# Sheet1.net
KiCad netlist of a schematic drawn in Altium Designer
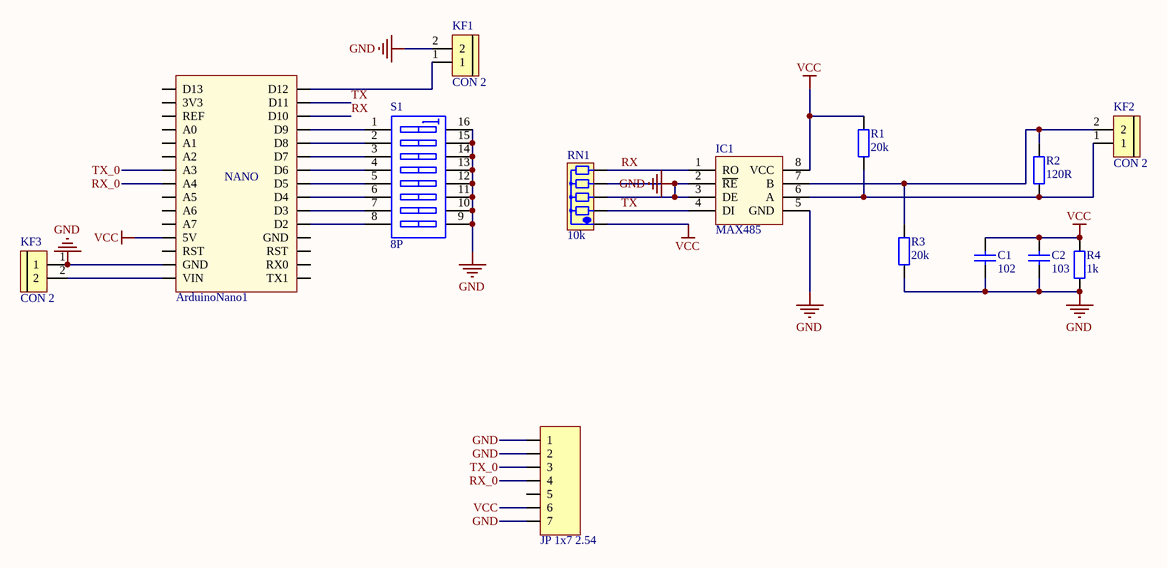
[diagram p0: Sheet1.SchDoc]

(export (version "E")
  (design (tool "Eeschema 10.0.6"))
  (components
    (comp (ref "ArduinoNano1")
      (value "Arduino Nano")
      (footprint "Arduino Nano")
      (description "Arduino NANO")
      (libsource (lib "LIBRARY") (part "Arduino Nano"))
    )
    (comp (ref "C1")
      (value "102")
      (footprint "tu gom")
      (description "Cắm")
      (libsource (lib "Altium_Lib_by_KhueNguyenCreator") (part "Tu gom 102 50V"))
    )
    (comp (ref "C2")
      (value "103")
      (footprint "tu gom")
      (description "Cắm")
      (libsource (lib "Altium_Lib_by_KhueNguyenCreator") (part "Tu gom 103 50V"))
    )
    (comp (ref "IC1")
      (value "MAX485")
      (footprint "DIP8/W0.3")
      (description "RS232 - RS485 (Same sn75176)")
      (libsource (lib "My Library") (part "MAX485"))
    )
    (comp (ref "JP1")
      (value "JP 1x7 2.54")
      (footprint "JP 1x7 CT")
      (description "Cắm")
      (libsource (lib "Altium_Lib_by_KhueNguyenCreator") (part "JP 1x7 2.54 Cai Thang"))
    )
    (comp (ref "KF1")
      (value "CON 2")
      (footprint "Con 2 KF301 5.08")
      (description "Cắm")
      (libsource (lib "Altium_Lib_by_KhueNguyenCreator") (part "CON 2 KF301"))
    )
    (comp (ref "KF2")
      (value "CON 2")
      (footprint "Con 2 KF301 5.08")
      (description "Cắm")
      (libsource (lib "Altium_Lib_by_KhueNguyenCreator") (part "CON 2 KF301"))
    )
    (comp (ref "KF3")
      (value "CON 2")
      (footprint "Con 2 KF301 5.08")
      (description "Cắm")
      (libsource (lib "") (part "CON 2 KF301_1"))
    )
    (comp (ref "R1")
      (value "20k")
      (footprint "tro vach 1/4w")
      (description "Cắm")
      (libsource (lib "Altium_Lib_by_KhueNguyenCreator") (part "Tro Vach 1/4W 5% 20k"))
    )
    (comp (ref "R2")
      (value "120R")
      (footprint "tro vach 1/4w")
      (description "Cắm")
      (libsource (lib "Altium_Lib_by_KhueNguyenCreator") (part "Tro Vach 1/4W 5% 120R"))
    )
    (comp (ref "R3")
      (value "20k")
      (footprint "tro vach 1/4w")
      (description "Cắm")
      (libsource (lib "Altium_Lib_by_KhueNguyenCreator") (part "Tro Vach 1/4W 5% 20k"))
    )
    (comp (ref "R4")
      (value "1k")
      (footprint "tro vach 1/4w")
      (description "Cắm")
      (libsource (lib "Altium_Lib_by_KhueNguyenCreator") (part "Tro Vach 1/4W 5% 1k"))
    )
    (comp (ref "RN1")
      (value "10k")
      (footprint "RN4")
      (description "Resistor 4 (thanh)")
      (libsource (lib "Cty1") (part "RN4"))
    )
    (comp (ref "S1")
      (value "8P")
      (footprint "SW-DIP8")
      (description "Cắm")
      (libsource (lib "THU VIEN SCH") (part "Cong Tac Bits 8P"))
    )
  )
  (nets
    (net (code "1") (name "/RX") (class "Default")
      (node (ref "ArduinoNano1") (pin "D10") (pinfunction "D10_D10") (pintype "passive"))
      (node (ref "IC1") (pin "1") (pinfunction "RO_1") (pintype "passive"))
      (node (ref "RN1") (pin "5") (pinfunction "5_5") (pintype "passive"))
    )
    (net (code "2") (name "/RX_0") (class "Default")
      (node (ref "ArduinoNano1") (pin "A4") (pinfunction "A4_A4") (pintype "passive"))
      (node (ref "JP1") (pin "4") (pinfunction "4_4") (pintype "passive"))
    )
    (net (code "3") (name "/TX") (class "Default")
      (node (ref "ArduinoNano1") (pin "D11") (pinfunction "D11_D11") (pintype "passive"))
      (node (ref "IC1") (pin "4") (pinfunction "DI_4") (pintype "passive"))
      (node (ref "RN1") (pin "2") (pinfunction "2_2") (pintype "passive"))
    )
    (net (code "4") (name "/TX_0") (class "Default")
      (node (ref "ArduinoNano1") (pin "A3") (pinfunction "A3_A3") (pintype "passive"))
      (node (ref "JP1") (pin "3") (pinfunction "3_3") (pintype "passive"))
    )
    (net (code "5") (name "GND") (class "Default")
      (node (ref "ArduinoNano1") (pin "GND") (pinfunction "GND_GND") (pintype "passive"))
      (node (ref "C1") (pin "2") (pinfunction "2_2") (pintype "passive"))
      (node (ref "C2") (pin "2") (pinfunction "2_2") (pintype "passive"))
      (node (ref "IC1") (pin "2") (pinfunction "~{RE}_2") (pintype "passive"))
      (node (ref "IC1") (pin "3") (pinfunction "DE_3") (pintype "passive"))
      (node (ref "IC1") (pin "5") (pinfunction "GND_5") (pintype "passive"))
      (node (ref "JP1") (pin "1") (pinfunction "1_1") (pintype "passive"))
      (node (ref "JP1") (pin "2") (pinfunction "2_2") (pintype "passive"))
      (node (ref "JP1") (pin "7") (pinfunction "7_7") (pintype "passive"))
      (node (ref "KF1") (pin "2") (pinfunction "2_2") (pintype "passive"))
      (node (ref "KF3") (pin "1") (pinfunction "1_1") (pintype "passive"))
      (node (ref "R3") (pin "1") (pinfunction "1_1") (pintype "passive"))
      (node (ref "R4") (pin "1") (pinfunction "1_1") (pintype "passive"))
      (node (ref "RN1") (pin "3") (pinfunction "3_3") (pintype "passive"))
      (node (ref "RN1") (pin "4") (pinfunction "4_4") (pintype "passive"))
      (node (ref "S1") (pin "10") (pinfunction "B7_10") (pintype "passive"))
      (node (ref "S1") (pin "11") (pinfunction "B6_11") (pintype "passive"))
      (node (ref "S1") (pin "12") (pinfunction "B5_12") (pintype "passive"))
      (node (ref "S1") (pin "13") (pinfunction "B4_13") (pintype "passive"))
      (node (ref "S1") (pin "14") (pinfunction "B3_14") (pintype "passive"))
      (node (ref "S1") (pin "15") (pinfunction "B2_15") (pintype "passive"))
      (node (ref "S1") (pin "16") (pinfunction "B1_16") (pintype "passive"))
      (node (ref "S1") (pin "9") (pinfunction "B8_9") (pintype "passive"))
    )
    (net (code "6") (name "Net-(ArduinoNano1-PadD12)") (class "Default")
      (node (ref "ArduinoNano1") (pin "D12") (pinfunction "D12_D12") (pintype "passive"))
      (node (ref "KF1") (pin "1") (pinfunction "1_1") (pintype "passive"))
    )
    (net (code "7") (name "Net-(ArduinoNano1-PadVIN)") (class "Default")
      (node (ref "ArduinoNano1") (pin "VIN") (pinfunction "VIN_VIN") (pintype "passive"))
      (node (ref "KF3") (pin "2") (pinfunction "2_2") (pintype "passive"))
    )
    (net (code "8") (name "Net-(IC1-A)") (class "Default")
      (node (ref "IC1") (pin "6") (pinfunction "A_6") (pintype "passive"))
      (node (ref "KF2") (pin "1") (pinfunction "1_1") (pintype "passive"))
      (node (ref "R1") (pin "1") (pinfunction "1_1") (pintype "passive"))
      (node (ref "R2") (pin "1") (pinfunction "1_1") (pintype "passive"))
    )
    (net (code "9") (name "Net-(IC1-B)") (class "Default")
      (node (ref "IC1") (pin "7") (pinfunction "B_7") (pintype "passive"))
      (node (ref "KF2") (pin "2") (pinfunction "2_2") (pintype "passive"))
      (node (ref "R2") (pin "2") (pinfunction "2_2") (pintype "passive"))
      (node (ref "R3") (pin "2") (pinfunction "2_2") (pintype "passive"))
    )
    (net (code "10") (name "Net-(S1-A1)") (class "Default")
      (node (ref "ArduinoNano1") (pin "D9") (pinfunction "D9_D9") (pintype "passive"))
      (node (ref "S1") (pin "1") (pinfunction "A1_1") (pintype "passive"))
    )
    (net (code "11") (name "Net-(S1-A2)") (class "Default")
      (node (ref "ArduinoNano1") (pin "D8") (pinfunction "D8_D8") (pintype "passive"))
      (node (ref "S1") (pin "2") (pinfunction "A2_2") (pintype "passive"))
    )
    (net (code "12") (name "Net-(S1-A3)") (class "Default")
      (node (ref "ArduinoNano1") (pin "D7") (pinfunction "D7_D7") (pintype "passive"))
      (node (ref "S1") (pin "3") (pinfunction "A3_3") (pintype "passive"))
    )
    (net (code "13") (name "Net-(S1-A4)") (class "Default")
      (node (ref "ArduinoNano1") (pin "D6") (pinfunction "D6_D6") (pintype "passive"))
      (node (ref "S1") (pin "4") (pinfunction "A4_4") (pintype "passive"))
    )
    (net (code "14") (name "Net-(S1-A5)") (class "Default")
      (node (ref "ArduinoNano1") (pin "D5") (pinfunction "D5_D5") (pintype "passive"))
      (node (ref "S1") (pin "5") (pinfunction "A5_5") (pintype "passive"))
    )
    (net (code "15") (name "Net-(S1-A6)") (class "Default")
      (node (ref "ArduinoNano1") (pin "D4") (pinfunction "D4_D4") (pintype "passive"))
      (node (ref "S1") (pin "6") (pinfunction "A6_6") (pintype "passive"))
    )
    (net (code "16") (name "Net-(S1-A7)") (class "Default")
      (node (ref "ArduinoNano1") (pin "D3") (pinfunction "D3_D3") (pintype "passive"))
      (node (ref "S1") (pin "7") (pinfunction "A7_7") (pintype "passive"))
    )
    (net (code "17") (name "Net-(S1-A8)") (class "Default")
      (node (ref "ArduinoNano1") (pin "D2") (pinfunction "D2_D2") (pintype "passive"))
      (node (ref "S1") (pin "8") (pinfunction "A8_8") (pintype "passive"))
    )
    (net (code "18") (name "VCC") (class "Default")
      (node (ref "ArduinoNano1") (pin "5V") (pinfunction "5V_5V") (pintype "passive"))
      (node (ref "C1") (pin "1") (pinfunction "1_1") (pintype "passive"))
      (node (ref "C2") (pin "1") (pinfunction "1_1") (pintype "passive"))
      (node (ref "IC1") (pin "8") (pinfunction "VCC_8") (pintype "passive"))
      (node (ref "JP1") (pin "6") (pinfunction "6_6") (pintype "passive"))
      (node (ref "R1") (pin "2") (pinfunction "2_2") (pintype "passive"))
      (node (ref "R4") (pin "2") (pinfunction "2_2") (pintype "passive"))
      (node (ref "RN1") (pin "1") (pinfunction "1_1") (pintype "passive"))
    )
    (net (code "19") (name "unconnected-(ArduinoNano1-Pad3V3)") (class "Default")
      (node (ref "ArduinoNano1") (pin "3V3") (pinfunction "3V3_3V3") (pintype "passive"))
    )
    (net (code "20") (name "unconnected-(ArduinoNano1-PadA0)") (class "Default")
      (node (ref "ArduinoNano1") (pin "A0") (pinfunction "A0_A0") (pintype "passive"))
    )
    (net (code "21") (name "unconnected-(ArduinoNano1-PadA1)") (class "Default")
      (node (ref "ArduinoNano1") (pin "A1") (pinfunction "A1_A1") (pintype "passive"))
    )
    (net (code "22") (name "unconnected-(ArduinoNano1-PadA2)") (class "Default")
      (node (ref "ArduinoNano1") (pin "A2") (pinfunction "A2_A2") (pintype "passive"))
    )
    (net (code "23") (name "unconnected-(ArduinoNano1-PadA5)") (class "Default")
      (node (ref "ArduinoNano1") (pin "A5") (pinfunction "A5_A5") (pintype "passive"))
    )
    (net (code "24") (name "unconnected-(ArduinoNano1-PadA6)") (class "Default")
      (node (ref "ArduinoNano1") (pin "A6") (pinfunction "A6_A6") (pintype "passive"))
    )
    (net (code "25") (name "unconnected-(ArduinoNano1-PadA7)") (class "Default")
      (node (ref "ArduinoNano1") (pin "A7") (pinfunction "A7_A7") (pintype "passive"))
    )
    (net (code "26") (name "unconnected-(ArduinoNano1-PadD13)") (class "Default")
      (node (ref "ArduinoNano1") (pin "D13") (pinfunction "D13_D13") (pintype "passive"))
    )
    (net (code "27") (name "unconnected-(ArduinoNano1-PadGND)") (class "Default")
      (node (ref "ArduinoNano1") (pin "GND") (pinfunction "GND_GND") (pintype "passive"))
    )
    (net (code "28") (name "unconnected-(ArduinoNano1-PadREF)") (class "Default")
      (node (ref "ArduinoNano1") (pin "REF") (pinfunction "REF_REF") (pintype "passive"))
    )
    (net (code "29") (name "unconnected-(ArduinoNano1-PadRST)") (class "Default")
      (node (ref "ArduinoNano1") (pin "RST") (pinfunction "RST_RST") (pintype "passive"))
    )
    (net (code "30") (name "unconnected-(ArduinoNano1-PadRST)_1") (class "Default")
      (node (ref "ArduinoNano1") (pin "RST") (pinfunction "RST_RST") (pintype "passive"))
    )
    (net (code "31") (name "unconnected-(ArduinoNano1-PadRX0)") (class "Default")
      (node (ref "ArduinoNano1") (pin "RX0") (pinfunction "RX0_RX0") (pintype "passive"))
    )
    (net (code "32") (name "unconnected-(ArduinoNano1-PadTX1)") (class "Default")
      (node (ref "ArduinoNano1") (pin "TX1") (pinfunction "TX1_TX1") (pintype "passive"))
    )
    (net (code "33") (name "unconnected-(JP1-Pad5)") (class "Default")
      (node (ref "JP1") (pin "5") (pinfunction "5_5") (pintype "passive"))
    )
  )
)
